# Water_Control.net
KiCad netlist of a schematic drawn in Altium Designer
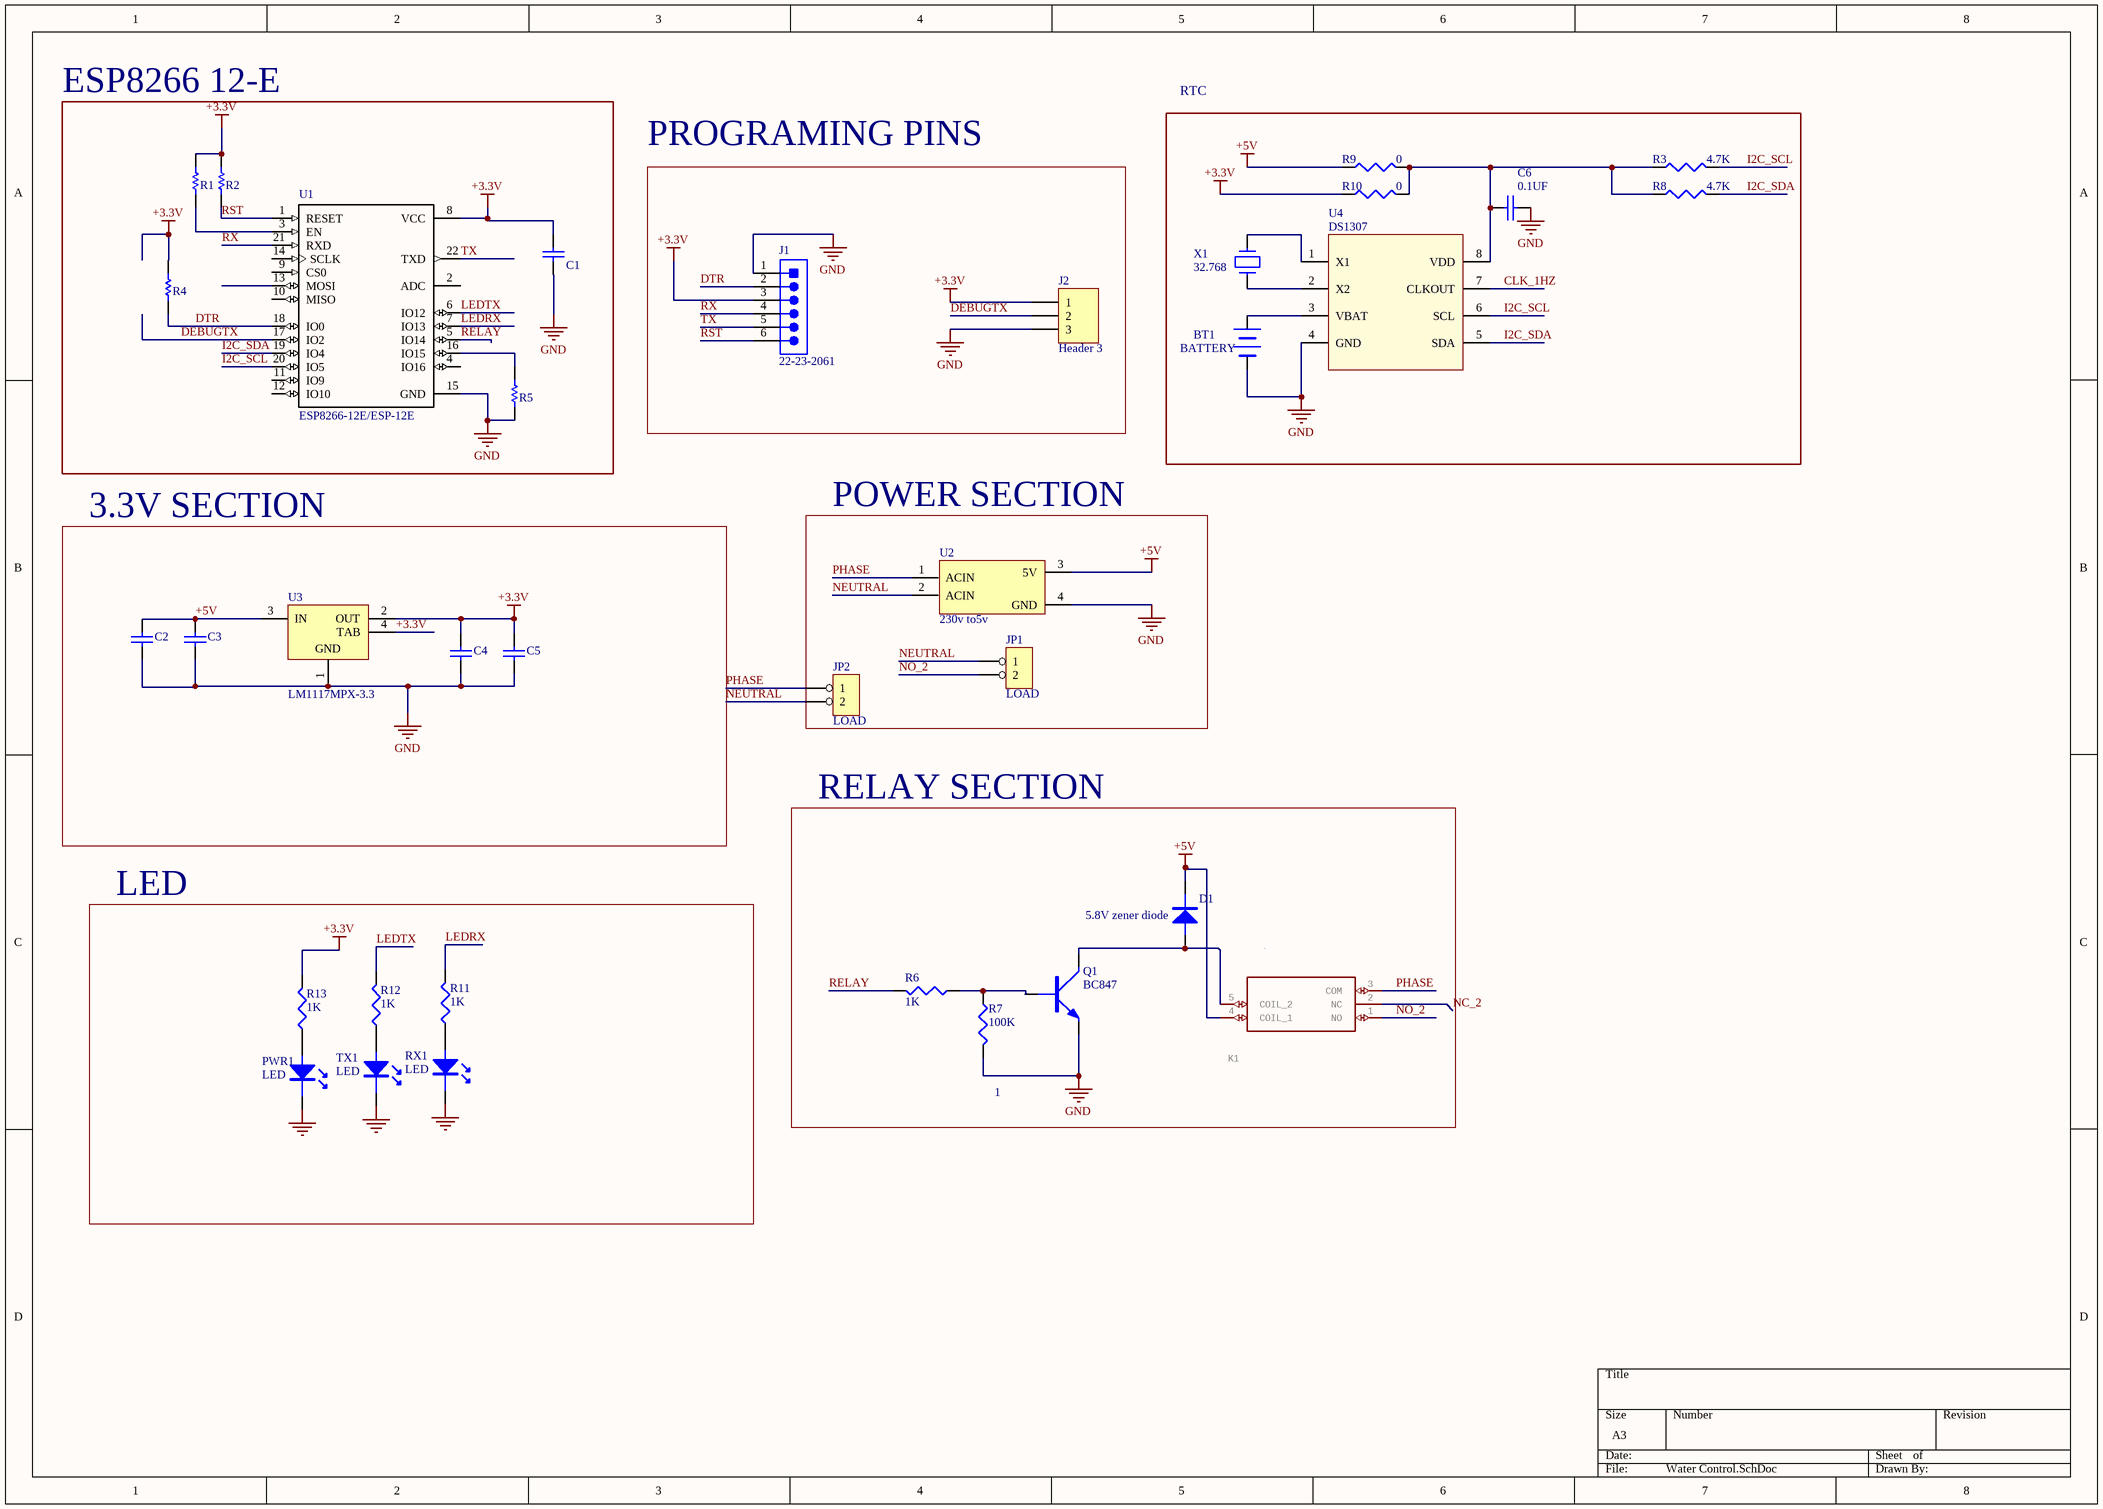
[diagram p0: Water Control.SchDoc]

(export (version "E")
  (design (tool "Eeschema 10.0.6"))
  (components
    (comp (ref "BT1")
      (value "BATTERY")
      (footprint "CR2032_HOLDER_CH28")
      (libsource (lib "Devices") (part "BATTERY"))
    )
    (comp (ref "C1")
      (value "08055C104KAJ2A")
      (footprint "CAPC0805")
      (fields (field (name "MANUFACTURER") "AVX Interconnect / Elco"))
      (libsource (lib "Miscellaneous Devices") (part "CAP"))
    )
    (comp (ref "C2")
      (value "CAP 2.7uF 10V 1206(3216)")
      (footprint "CAPC1206(3216)110_L")
      (description "CAP 2.7uF 10V ±10% 1206 (3216 Metric) Thickness 1.05mm SMD")
      (fields (field (name "TOLERANCE") "Â±10%"))
      (libsource (lib "Altium Content Vault") (part "CAP"))
    )
    (comp (ref "C3")
      (value "CAP 2.7uF 10V 1206(3216)")
      (footprint "CAPC1206(3216)110_L")
      (description "CAP 2.7uF 10V ±10% 1206 (3216 Metric) Thickness 1.05mm SMD")
      (fields (field (name "TOLERANCE") "Â±10%"))
      (libsource (lib "Altium Content Vault") (part "CAP"))
    )
    (comp (ref "C4")
      (value "CAP 2.7uF 10V 1206(3216)")
      (footprint "CAPC1206(3216)110_L")
      (description "CAP 2.7uF 10V ±10% 1206 (3216 Metric) Thickness 1.05mm SMD")
      (fields (field (name "TOLERANCE") "Â±10%"))
      (libsource (lib "Altium Content Vault") (part "CAP"))
    )
    (comp (ref "C5")
      (value "CAP 2.7uF 10V 1206(3216)")
      (footprint "CAPC1206(3216)110_L")
      (description "CAP 2.7uF 10V ±10% 1206 (3216 Metric) Thickness 1.05mm SMD")
      (fields (field (name "TOLERANCE") "Â±10%"))
      (libsource (lib "Altium Content Vault") (part "CAP"))
    )
    (comp (ref "C6") (value "0.1UF") (footprint "CAPC0805") (libsource (lib "Devices") (part "CAP NP")))
    (comp (ref "D1")
      (value "5.8V zener diode")
      (footprint "BZT55B13GS08")
      (libsource (lib "Devices") (part "DIODE"))
    )
    (comp (ref "J1")
      (value "22-23-2061")
      (footprint "HDR1X6")
      (fields (field (name "MANUFACTURER") "Molex"))
      (libsource (lib "Miscellaneous Connectors") (part "CN-1P-M-R6"))
    )
    (comp (ref "J2")
      (value "Header 3")
      (footprint "HDR1X3")
      (description "Header, 3-Pin")
      (fields (field (name "PUBLISHER") "Altium Limited"))
      (libsource (lib "Miscellaneous Connectors") (part "Header 3"))
    )
    (comp (ref "JP1") (value "LOAD") (footprint "10 mm pitch") (libsource (lib "Devices") (part "HEADER 2")))
    (comp (ref "JP2") (value "LOAD") (footprint "10 mm pitch") (libsource (lib "Devices") (part "HEADER 2")))
    (comp (ref "K1")
      (value "Relays General Purpose Non Latching 12VDC SPDT 30A 250VAC Through Hole RoHS   Source:  Datasheet")
      (footprint "R53G112DF1S")
      (fields (field (name "MANUFACTURER_PART_NUMBER") "R53G-112DF-1-S"))
      (libsource (lib "R53G-112DF-1-S") (part "R53G-112DF-1-S"))
    )
    (comp (ref "PWR1") (value "LED") (footprint "Type 3mm") (libsource (lib "Devices") (part "LED")))
    (comp (ref "Q1") (value "BC847") (footprint "SOT23-3") (libsource (lib "Devices") (part "NPN BEC")))
    (comp (ref "R1")
      (value "2R55 1% 0805(2012)")
      (footprint "RESC0805(2012)_L")
      (description "2R55 0.125W 1% 0805 (2012 Metric)  SMD")
      (fields (field (name "TOLERANCE") "1 %") (field (name "POWER") "0.125 W"))
      (libsource (lib "Altium Content Vault") (part "RES"))
    )
    (comp (ref "R2")
      (value "2R55 1% 0805(2012)")
      (footprint "RESC0805(2012)_L")
      (description "2R55 0.125W 1% 0805 (2012 Metric)  SMD")
      (fields (field (name "TOLERANCE") "1 %") (field (name "POWER") "0.125 W"))
      (libsource (lib "Altium Content Vault") (part "RES"))
    )
    (comp (ref "R3")
      (value "4.7K")
      (footprint "RESC0805")
      (description "RESISTOR")
      (libsource (lib "Components - 22.01.19 - 11.39") (part "RES1"))
    )
    (comp (ref "R4")
      (value "2R55 1% 0805(2012)")
      (footprint "RESC0805(2012)_L")
      (description "2R55 0.125W 1% 0805 (2012 Metric)  SMD")
      (fields (field (name "TOLERANCE") "1 %") (field (name "POWER") "0.125 W"))
      (libsource (lib "Altium Content Vault") (part "RES"))
    )
    (comp (ref "R5")
      (value "2R55 1% 0805(2012)")
      (footprint "RESC0805(2012)_L")
      (description "2R55 0.125W 1% 0805 (2012 Metric)  SMD")
      (fields (field (name "TOLERANCE") "1 %") (field (name "POWER") "0.125 W"))
      (libsource (lib "Altium Content Vault") (part "RES"))
    )
    (comp (ref "R6")
      (value "1K")
      (footprint "RESC0805")
      (description "RESISTOR")
      (libsource (lib "Devices") (part "RES1"))
    )
    (comp (ref "R7")
      (value "100K")
      (footprint "RESC0805")
      (description "RESISTOR")
      (libsource (lib "Devices") (part "RES1"))
    )
    (comp (ref "R8")
      (value "4.7K")
      (footprint "RESC0805")
      (description "RESISTOR")
      (libsource (lib "Components - 22.01.19 - 11.39") (part "RES1"))
    )
    (comp (ref "R9")
      (value "0")
      (footprint "RESC0805")
      (description "RESISTOR")
      (libsource (lib "Components - 22.01.19 - 11.39") (part "RES1"))
    )
    (comp (ref "R10")
      (value "0")
      (footprint "RESC0805")
      (description "RESISTOR")
      (libsource (lib "Components - 22.01.19 - 11.39") (part "RES1"))
    )
    (comp (ref "R11")
      (value "1K")
      (footprint "RESC0805")
      (description "RESISTOR")
      (libsource (lib "Devices") (part "RES1"))
    )
    (comp (ref "R12")
      (value "1K")
      (footprint "RESC0805")
      (description "RESISTOR")
      (libsource (lib "Devices") (part "RES1"))
    )
    (comp (ref "R13")
      (value "1K")
      (footprint "RESC0805")
      (description "RESISTOR")
      (libsource (lib "Devices") (part "RES1"))
    )
    (comp (ref "RX1") (value "LED") (footprint "Type 3mm") (libsource (lib "Devices") (part "LED")))
    (comp (ref "TX1") (value "LED") (footprint "Type 3mm") (libsource (lib "Devices") (part "LED")))
    (comp (ref "U1")
      (value "ESP8266-12E/ESP-12E")
      (footprint "*XCVR_ESP8266-12E/ESP-12E")
      (fields (field (name "MF") "AI-Thinker"))
      (libsource (lib "ESP8266-12E_ESP-12E") (part "ESP8266-12E/ESP-12E"))
    )
    (comp (ref "U2")
      (value "230v to5v")
      (footprint "230V-5V")
      (libsource (lib "KishanLibray") (part "230v to5v"))
    )
    (comp (ref "U3")
      (value "LM1117MPX-3.3")
      (footprint "MP04A_N")
      (description "800mA Low-Dropout Linear Regulator, 4-pin SOT-223")
      (fields (field (name "MANUFACTURER") "National Semiconductor"))
      (libsource (lib "Altium Content Vault") (part "PM-REG-LM1086-SOT4"))
    )
    (comp (ref "U4") (value "DS1307") (footprint "SOIC8") (libsource (lib "CustomParts") (part "DS1307")))
    (comp (ref "X1")
      (value "32.768")
      (footprint "CRYSTAL_32.768_SMD")
      (libsource (lib "Devices") (part "CRYSTAL"))
    )
  )
  (nets
    (net (code "1") (name "+3.3V") (class "Default")
      (node (ref "C1") (pin "1") (pinfunction "1_1") (pintype "passive"))
      (node (ref "C4") (pin "2") (pinfunction "2_2") (pintype "passive"))
      (node (ref "C5") (pin "2") (pinfunction "2_2") (pintype "passive"))
      (node (ref "J1") (pin "3") (pinfunction "3_3") (pintype "passive"))
      (node (ref "J2") (pin "1") (pinfunction "1_1") (pintype "passive"))
      (node (ref "R1") (pin "2") (pinfunction "2_2") (pintype "passive"))
      (node (ref "R10") (pin "1") (pintype "passive"))
      (node (ref "R13") (pin "2") (pintype "passive"))
      (node (ref "R2") (pin "2") (pinfunction "2_2") (pintype "passive"))
      (node (ref "R4") (pin "2") (pinfunction "2_2") (pintype "passive"))
      (node (ref "U1") (pin "8") (pinfunction "VCC_8") (pintype "power_in"))
      (node (ref "U3") (pin "2") (pinfunction "OUT_2") (pintype "power_in"))
      (node (ref "U3") (pin "4") (pinfunction "TAB_4") (pintype "power_in"))
    )
    (net (code "2") (name "+5V") (class "Default")
      (node (ref "C2") (pin "2") (pinfunction "2_2") (pintype "passive"))
      (node (ref "C3") (pin "2") (pinfunction "2_2") (pintype "passive"))
      (node (ref "D1") (pin "2") (pinfunction "2_2") (pintype "passive"))
      (node (ref "K1") (pin "4") (pinfunction "COIL_1_4") (pintype "bidirectional"))
      (node (ref "R9") (pin "1") (pintype "passive"))
      (node (ref "U2") (pin "3") (pinfunction "5V_3") (pintype "passive"))
      (node (ref "U3") (pin "3") (pinfunction "IN_3") (pintype "power_in"))
    )
    (net (code "3") (name "/CLK_1HZ") (class "Default")
      (node (ref "U4") (pin "7") (pinfunction "CLKOUT_7") (pintype "passive"))
    )
    (net (code "4") (name "/DEBUGT~{X}") (class "Default")
      (node (ref "J2") (pin "2") (pinfunction "2_2") (pintype "passive"))
      (node (ref "U1") (pin "17") (pinfunction "IO2_17") (pintype "bidirectional"))
    )
    (net (code "5") (name "/DTR") (class "Default")
      (node (ref "J1") (pin "2") (pinfunction "2_2") (pintype "passive"))
      (node (ref "R4") (pin "1") (pinfunction "1_1") (pintype "passive"))
      (node (ref "U1") (pin "18") (pinfunction "IO0_18") (pintype "bidirectional"))
    )
    (net (code "6") (name "/I2C_SCL") (class "Default")
      (node (ref "R3") (pin "2") (pintype "passive"))
      (node (ref "U1") (pin "20") (pinfunction "IO5_20") (pintype "bidirectional"))
      (node (ref "U4") (pin "6") (pinfunction "SCL_6") (pintype "passive"))
    )
    (net (code "7") (name "/I2C_SDA") (class "Default")
      (node (ref "R8") (pin "2") (pintype "passive"))
      (node (ref "U1") (pin "19") (pinfunction "IO4_19") (pintype "bidirectional"))
      (node (ref "U4") (pin "5") (pinfunction "SDA_5") (pintype "passive"))
    )
    (net (code "8") (name "/LEDRX") (class "Default")
      (node (ref "R11") (pin "2") (pintype "passive"))
      (node (ref "U1") (pin "7") (pinfunction "IO13_7") (pintype "bidirectional"))
    )
    (net (code "9") (name "/LEDTX") (class "Default")
      (node (ref "R12") (pin "2") (pintype "passive"))
      (node (ref "U1") (pin "6") (pinfunction "IO12_6") (pintype "bidirectional"))
    )
    (net (code "10") (name "/NC_2") (class "Default")
      (node (ref "K1") (pin "2") (pinfunction "NC_2") (pintype "passive"))
    )
    (net (code "11") (name "/NEUTRAL") (class "Default")
      (node (ref "JP1") (pin "1") (pinfunction "1_1") (pintype "passive"))
      (node (ref "JP2") (pin "2") (pinfunction "2_2") (pintype "passive"))
      (node (ref "U2") (pin "2") (pinfunction "ACIN_2") (pintype "passive"))
    )
    (net (code "12") (name "/NO_2") (class "Default")
      (node (ref "JP1") (pin "2") (pinfunction "2_2") (pintype "passive"))
      (node (ref "K1") (pin "1") (pinfunction "NO_1") (pintype "bidirectional"))
    )
    (net (code "13") (name "/PHASE") (class "Default")
      (node (ref "JP2") (pin "1") (pinfunction "1_1") (pintype "passive"))
      (node (ref "K1") (pin "3") (pinfunction "COM_3") (pintype "bidirectional"))
      (node (ref "U2") (pin "1") (pinfunction "ACIN_1") (pintype "passive"))
    )
    (net (code "14") (name "/RELAY") (class "Default")
      (node (ref "R6") (pin "2") (pintype "passive"))
      (node (ref "U1") (pin "5") (pinfunction "IO14_5") (pintype "bidirectional"))
    )
    (net (code "15") (name "/RST") (class "Default")
      (node (ref "J1") (pin "6") (pinfunction "6_6") (pintype "passive"))
      (node (ref "R2") (pin "1") (pinfunction "1_1") (pintype "passive"))
      (node (ref "U1") (pin "1") (pinfunction "RESET_1") (pintype "input"))
    )
    (net (code "16") (name "/RX") (class "Default")
      (node (ref "J1") (pin "4") (pinfunction "4_4") (pintype "passive"))
      (node (ref "U1") (pin "21") (pinfunction "RXD_21") (pintype "input"))
    )
    (net (code "17") (name "/TX") (class "Default")
      (node (ref "J1") (pin "5") (pinfunction "5_5") (pintype "passive"))
      (node (ref "U1") (pin "22") (pinfunction "TXD_22") (pintype "output"))
    )
    (net (code "18") (name "GND") (class "Default")
      (node (ref "BT1") (pin "2") (pintype "passive"))
      (node (ref "C1") (pin "2") (pinfunction "2_2") (pintype "passive"))
      (node (ref "C2") (pin "1") (pinfunction "1_1") (pintype "passive"))
      (node (ref "C3") (pin "1") (pinfunction "1_1") (pintype "passive"))
      (node (ref "C4") (pin "1") (pinfunction "1_1") (pintype "passive"))
      (node (ref "C5") (pin "1") (pinfunction "1_1") (pintype "passive"))
      (node (ref "C6") (pin "1") (pintype "passive"))
      (node (ref "J1") (pin "1") (pinfunction "1_1") (pintype "passive"))
      (node (ref "J2") (pin "3") (pinfunction "3_3") (pintype "passive"))
      (node (ref "PWR1") (pin "2") (pinfunction "K_2") (pintype "passive"))
      (node (ref "Q1") (pin "2") (pinfunction "EMIT_2") (pintype "passive"))
      (node (ref "R5") (pin "1") (pinfunction "1_1") (pintype "passive"))
      (node (ref "R7") (pin "2") (pintype "passive"))
      (node (ref "RX1") (pin "2") (pinfunction "K_2") (pintype "passive"))
      (node (ref "TX1") (pin "2") (pinfunction "K_2") (pintype "passive"))
      (node (ref "U1") (pin "15") (pinfunction "GND_15") (pintype "power_in"))
      (node (ref "U2") (pin "4") (pinfunction "GND_4") (pintype "passive"))
      (node (ref "U3") (pin "1") (pinfunction "GND_1") (pintype "power_in"))
      (node (ref "U4") (pin "4") (pinfunction "GND_4") (pintype "passive"))
    )
    (net (code "19") (name "Net-(K1-COIL_2)") (class "Default")
      (node (ref "D1") (pin "1") (pinfunction "1_1") (pintype "passive"))
      (node (ref "K1") (pin "5") (pinfunction "COIL_2_5") (pintype "bidirectional"))
      (node (ref "Q1") (pin "3") (pinfunction "COLL_3") (pintype "passive"))
    )
    (net (code "20") (name "Net-(PWR1-A)") (class "Default")
      (node (ref "PWR1") (pin "1") (pinfunction "A_1") (pintype "passive"))
      (node (ref "R13") (pin "1") (pintype "passive"))
    )
    (net (code "21") (name "Net-(Q1-BASE)") (class "Default")
      (node (ref "Q1") (pin "1") (pinfunction "BASE_1") (pintype "passive"))
      (node (ref "R6") (pin "1") (pintype "passive"))
      (node (ref "R7") (pin "1") (pintype "passive"))
    )
    (net (code "22") (name "Net-(RX1-A)") (class "Default")
      (node (ref "R11") (pin "1") (pintype "passive"))
      (node (ref "RX1") (pin "1") (pinfunction "A_1") (pintype "passive"))
    )
    (net (code "23") (name "Net-(TX1-A)") (class "Default")
      (node (ref "R12") (pin "1") (pintype "passive"))
      (node (ref "TX1") (pin "1") (pinfunction "A_1") (pintype "passive"))
    )
    (net (code "24") (name "Net-(U1-EN)") (class "Default")
      (node (ref "R1") (pin "1") (pinfunction "1_1") (pintype "passive"))
      (node (ref "U1") (pin "3") (pinfunction "EN_3") (pintype "input"))
    )
    (net (code "25") (name "Net-(U1-IO15)") (class "Default")
      (node (ref "R5") (pin "2") (pinfunction "2_2") (pintype "passive"))
      (node (ref "U1") (pin "16") (pinfunction "IO15_16") (pintype "bidirectional"))
    )
    (net (code "26") (name "Net-(U4-VBAT)") (class "Default")
      (node (ref "BT1") (pin "1") (pintype "passive"))
      (node (ref "U4") (pin "3") (pinfunction "VBAT_3") (pintype "passive"))
    )
    (net (code "27") (name "Net-(U4-VDD)") (class "Default")
      (node (ref "C6") (pin "2") (pintype "passive"))
      (node (ref "R10") (pin "2") (pintype "passive"))
      (node (ref "R3") (pin "1") (pintype "passive"))
      (node (ref "R8") (pin "1") (pintype "passive"))
      (node (ref "R9") (pin "2") (pintype "passive"))
      (node (ref "U4") (pin "8") (pinfunction "VDD_8") (pintype "passive"))
    )
    (net (code "28") (name "Net-(U4-X1)") (class "Default")
      (node (ref "U4") (pin "1") (pinfunction "X1_1") (pintype "passive"))
      (node (ref "X1") (pin "1") (pintype "passive"))
    )
    (net (code "29") (name "Net-(U4-X2)") (class "Default")
      (node (ref "U4") (pin "2") (pinfunction "X2_2") (pintype "passive"))
      (node (ref "X1") (pin "2") (pintype "passive"))
    )
    (net (code "30") (name "unconnected-(U1-ADC-Pad2)") (class "Default")
      (node (ref "U1") (pin "2") (pinfunction "ADC_2") (pintype "passive"))
    )
    (net (code "31") (name "unconnected-(U1-CS0-Pad9)") (class "Default")
      (node (ref "U1") (pin "9") (pinfunction "CS0_9") (pintype "input"))
    )
    (net (code "32") (name "unconnected-(U1-IO9-Pad11)") (class "Default")
      (node (ref "U1") (pin "11") (pinfunction "IO9_11") (pintype "bidirectional"))
    )
    (net (code "33") (name "unconnected-(U1-IO10-Pad12)") (class "Default")
      (node (ref "U1") (pin "12") (pinfunction "IO10_12") (pintype "bidirectional"))
    )
    (net (code "34") (name "unconnected-(U1-IO16-Pad4)") (class "Default")
      (node (ref "U1") (pin "4") (pinfunction "IO16_4") (pintype "bidirectional"))
    )
    (net (code "35") (name "unconnected-(U1-MISO-Pad10)") (class "Default")
      (node (ref "U1") (pin "10") (pinfunction "MISO_10") (pintype "bidirectional"))
    )
    (net (code "36") (name "unconnected-(U1-MOSI-Pad13)") (class "Default")
      (node (ref "U1") (pin "13") (pinfunction "MOSI_13") (pintype "bidirectional"))
    )
    (net (code "37") (name "unconnected-(U1-SCLK-Pad14)") (class "Default")
      (node (ref "U1") (pin "14") (pinfunction "SCLK_14") (pintype "input"))
    )
  )
)
